# JDM2_Low_Voltage.net
KiCad netlist of a schematic drawn in EAGLE
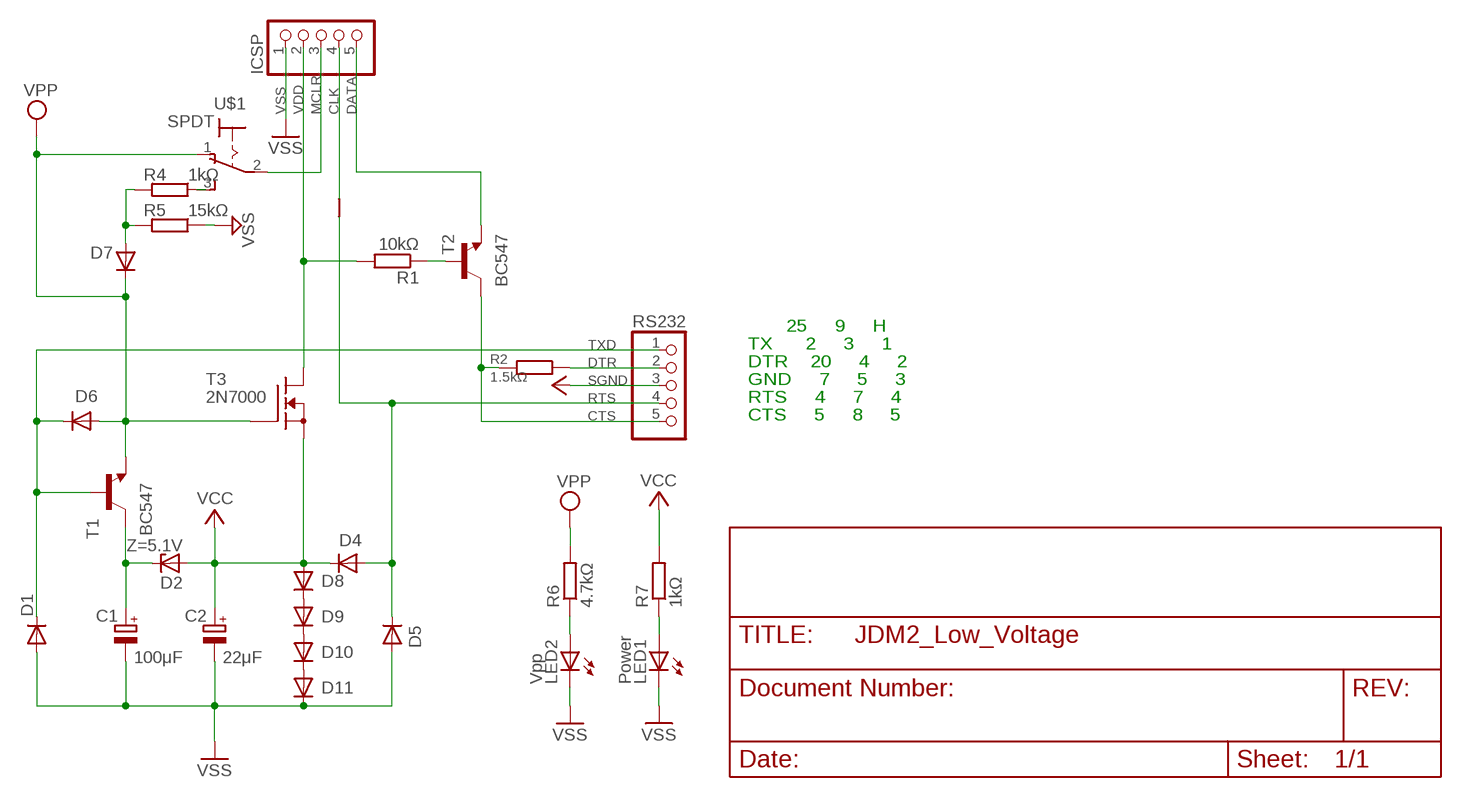
[diagram p0: schematic, sheet 1]

(export (version "E")
  (design (tool "Eeschema 10.0.6"))
  (components
    (comp (ref "C1")
      (value "100μF")
      (footprint "eagle-import:E2,5-5")
      (libsource (lib "eagle-import") (part "CPOL-EUE2.5-5"))
    )
    (comp (ref "C2")
      (value "22μF")
      (footprint "eagle-import:E2,5-5")
      (libsource (lib "eagle-import") (part "CPOL-EUE2.5-5"))
    )
    (comp (ref "D1")
      (value "1N4148")
      (footprint "eagle-import:DO35-7")
      (libsource (lib "eagle-import") (part "1N4148-7"))
    )
    (comp (ref "D2")
      (value "Z=5.1V")
      (footprint "eagle-import:DO35Z5")
      (libsource (lib "eagle-import") (part "Z-DIODEZ5"))
    )
    (comp (ref "D4")
      (value "1N4148")
      (footprint "eagle-import:DO35-2_54")
      (libsource (lib "eagle-import") (part "1N4148-2.54"))
    )
    (comp (ref "D5")
      (value "1N4148")
      (footprint "eagle-import:DO34-18")
      (libsource (lib "eagle-import") (part "1N4148-18"))
    )
    (comp (ref "D6")
      (value "1N4148")
      (footprint "eagle-import:DO35-2_54A")
      (libsource (lib "eagle-import") (part "1N4148-2.54A"))
    )
    (comp (ref "D7")
      (value "2N4148")
      (footprint "eagle-import:DO35-2_54A")
      (libsource (lib "eagle-import") (part "1N4148-2.54A"))
    )
    (comp (ref "D8")
      (value "1N4148")
      (footprint "eagle-import:DO35-2_54A")
      (libsource (lib "eagle-import") (part "1N4148-2.54A"))
    )
    (comp (ref "D9")
      (value "1N4148")
      (footprint "eagle-import:DO35-2_54A")
      (libsource (lib "eagle-import") (part "1N4148-2.54A"))
    )
    (comp (ref "D10")
      (value "1N4148")
      (footprint "eagle-import:DO35-2_54A")
      (libsource (lib "eagle-import") (part "1N4148-2.54A"))
    )
    (comp (ref "D11")
      (value "1N4148")
      (footprint "eagle-import:DO35-2_54A")
      (libsource (lib "eagle-import") (part "1N4148-2.54A"))
    )
    (comp (ref "ICSP")
      (value "PINHD-1X5")
      (footprint "eagle-import:1X05")
      (libsource (lib "eagle-import") (part "PINHD-1X5"))
    )
    (comp (ref "J1")
      (value "DUMMY")
      (footprint "eagle-import:DUMMY")
      (libsource (lib "eagle-import") (part "DUMMY"))
    )
    (comp (ref "LED1")
      (value "Power")
      (footprint "eagle-import:LED5MM")
      (libsource (lib "eagle-import") (part "LED"))
    )
    (comp (ref "LED2")
      (value "Vpp")
      (footprint "eagle-import:LED5MM")
      (libsource (lib "eagle-import") (part "LED"))
    )
    (comp (ref "R1")
      (value "10kΩ")
      (footprint "eagle-import:0207_10")
      (libsource (lib "eagle-import") (part "RES-0207-10"))
    )
    (comp (ref "R2")
      (value "1.5kΩ")
      (footprint "eagle-import:0204_7")
      (libsource (lib "eagle-import") (part "RES-0204-7"))
    )
    (comp (ref "R4")
      (value "1kΩ")
      (footprint "eagle-import:0207_10")
      (libsource (lib "eagle-import") (part "RES-0207-10"))
    )
    (comp (ref "R5")
      (value "15kΩ")
      (footprint "eagle-import:0207_10")
      (libsource (lib "eagle-import") (part "RES-0207-10"))
    )
    (comp (ref "R6")
      (value "4.7kΩ")
      (footprint "eagle-import:0204_7")
      (libsource (lib "eagle-import") (part "RES-0204-7"))
    )
    (comp (ref "R7")
      (value "1kΩ")
      (footprint "eagle-import:0204_7")
      (libsource (lib "eagle-import") (part "RES-0204-7"))
    )
    (comp (ref "RS232")
      (value "PINHD-1X5")
      (footprint "eagle-import:1X05")
      (libsource (lib "eagle-import") (part "PINHD-1X5"))
    )
    (comp (ref "T1")
      (value "BC547")
      (footprint "eagle-import:TO92-CBE")
      (libsource (lib "eagle-import") (part "BC547"))
    )
    (comp (ref "T2")
      (value "BC547")
      (footprint "eagle-import:TO92-CBE")
      (libsource (lib "eagle-import") (part "BC547"))
    )
    (comp (ref "T3")
      (value "2N7000")
      (footprint "eagle-import:TO92")
      (libsource (lib "eagle-import") (part "2N7000"))
    )
    (comp (ref "U$1")
      (value "SPDT")
      (footprint "eagle-import:SPDT")
      (libsource (lib "eagle-import") (part "SPDT"))
    )
  )
  (nets
    (net (code "1") (name "/CLK") (class "Default")
      (node (ref "ICSP") (pin "4") (pinfunction "4_4") (pintype "passive"))
      (node (ref "J1") (pin "2") (pinfunction "2_2") (pintype "passive"))
    )
    (net (code "2") (name "/CTS") (class "Default")
      (node (ref "R2") (pin "2") (pinfunction "2_2") (pintype "passive"))
      (node (ref "RS232") (pin "5") (pinfunction "5_5") (pintype "passive"))
      (node (ref "T2") (pin "C") (pinfunction "C_C") (pintype "passive"))
    )
    (net (code "3") (name "/DATA") (class "Default")
      (node (ref "ICSP") (pin "5") (pinfunction "5_5") (pintype "passive"))
      (node (ref "T2") (pin "E") (pinfunction "E_E") (pintype "passive"))
    )
    (net (code "4") (name "/DTR") (class "Default")
      (node (ref "R2") (pin "1") (pinfunction "1_1") (pintype "passive"))
      (node (ref "RS232") (pin "2") (pinfunction "2_2") (pintype "passive"))
    )
    (net (code "5") (name "/MCLR") (class "Default")
      (node (ref "ICSP") (pin "3") (pinfunction "3_3") (pintype "passive"))
      (node (ref "U$1") (pin "2") (pinfunction "P_2") (pintype "passive"))
    )
    (net (code "6") (name "/RTS") (class "Default")
      (node (ref "D4") (pin "A") (pinfunction "A_A") (pintype "passive"))
      (node (ref "D5") (pin "C") (pinfunction "C_C") (pintype "passive"))
      (node (ref "J1") (pin "1") (pinfunction "1_1") (pintype "passive"))
      (node (ref "RS232") (pin "4") (pinfunction "4_4") (pintype "passive"))
    )
    (net (code "7") (name "/TXD") (class "Default")
      (node (ref "D1") (pin "C") (pinfunction "C_C") (pintype "passive"))
      (node (ref "D6") (pin "C") (pinfunction "C_C") (pintype "passive"))
      (node (ref "RS232") (pin "1") (pinfunction "1_1") (pintype "passive"))
      (node (ref "T1") (pin "B") (pinfunction "B_B") (pintype "passive"))
    )
    (net (code "8") (name "/VDD") (class "Default")
      (node (ref "ICSP") (pin "2") (pinfunction "2_2") (pintype "passive"))
      (node (ref "R1") (pin "2") (pinfunction "2_2") (pintype "passive"))
      (node (ref "T3") (pin "3") (pinfunction "D_3") (pintype "passive"))
    )
    (net (code "9") (name "Net-(C1-Pad+)") (class "Default")
      (node (ref "C1") (pin "+") (pinfunction "+_+") (pintype "passive"))
      (node (ref "D2") (pin "C") (pinfunction "C_C") (pintype "passive"))
      (node (ref "T1") (pin "C") (pinfunction "C_C") (pintype "passive"))
    )
    (net (code "10") (name "Net-(D7-PadA)") (class "Default")
      (node (ref "D7") (pin "A") (pinfunction "A_A") (pintype "passive"))
      (node (ref "R4") (pin "2") (pinfunction "2_2") (pintype "passive"))
      (node (ref "R5") (pin "2") (pinfunction "2_2") (pintype "passive"))
    )
    (net (code "11") (name "Net-(D8-PadC)") (class "Default")
      (node (ref "D8") (pin "C") (pinfunction "C_C") (pintype "passive"))
      (node (ref "D9") (pin "A") (pinfunction "A_A") (pintype "passive"))
    )
    (net (code "12") (name "Net-(D10-PadA)") (class "Default")
      (node (ref "D10") (pin "A") (pinfunction "A_A") (pintype "passive"))
      (node (ref "D9") (pin "C") (pinfunction "C_C") (pintype "passive"))
    )
    (net (code "13") (name "Net-(D10-PadC)") (class "Default")
      (node (ref "D10") (pin "C") (pinfunction "C_C") (pintype "passive"))
      (node (ref "D11") (pin "A") (pinfunction "A_A") (pintype "passive"))
    )
    (net (code "14") (name "Net-(LED1-PadA)") (class "Default")
      (node (ref "LED1") (pin "A") (pinfunction "A_A") (pintype "passive"))
      (node (ref "R7") (pin "1") (pinfunction "1_1") (pintype "passive"))
    )
    (net (code "15") (name "Net-(LED2-PadA)") (class "Default")
      (node (ref "LED2") (pin "A") (pinfunction "A_A") (pintype "passive"))
      (node (ref "R6") (pin "1") (pinfunction "1_1") (pintype "passive"))
    )
    (net (code "16") (name "Net-(R1-Pad1)") (class "Default")
      (node (ref "R1") (pin "1") (pinfunction "1_1") (pintype "passive"))
      (node (ref "T2") (pin "B") (pinfunction "B_B") (pintype "passive"))
    )
    (net (code "17") (name "Net-(U$1-S)") (class "Default")
      (node (ref "R4") (pin "1") (pinfunction "1_1") (pintype "passive"))
      (node (ref "U$1") (pin "3") (pinfunction "S_3") (pintype "passive"))
    )
    (net (code "18") (name "VCC") (class "Default")
      (node (ref "C2") (pin "+") (pinfunction "+_+") (pintype "passive"))
      (node (ref "D2") (pin "A") (pinfunction "A_A") (pintype "passive"))
      (node (ref "D4") (pin "C") (pinfunction "C_C") (pintype "passive"))
      (node (ref "D8") (pin "A") (pinfunction "A_A") (pintype "passive"))
      (node (ref "R7") (pin "2") (pinfunction "2_2") (pintype "passive"))
      (node (ref "RS232") (pin "3") (pinfunction "3_3") (pintype "passive"))
      (node (ref "T3") (pin "1") (pinfunction "S_1") (pintype "passive"))
    )
    (net (code "19") (name "VPP") (class "Default")
      (node (ref "D6") (pin "A") (pinfunction "A_A") (pintype "passive"))
      (node (ref "D7") (pin "C") (pinfunction "C_C") (pintype "passive"))
      (node (ref "R6") (pin "2") (pinfunction "2_2") (pintype "passive"))
      (node (ref "T1") (pin "E") (pinfunction "E_E") (pintype "passive"))
      (node (ref "T3") (pin "2") (pinfunction "G_2") (pintype "passive"))
      (node (ref "U$1") (pin "1") (pinfunction "O_1") (pintype "passive"))
    )
    (net (code "20") (name "VSS") (class "Default")
      (node (ref "C1") (pin "-") (pinfunction "-_-") (pintype "passive"))
      (node (ref "C2") (pin "-") (pinfunction "-_-") (pintype "passive"))
      (node (ref "D1") (pin "A") (pinfunction "A_A") (pintype "passive"))
      (node (ref "D11") (pin "C") (pinfunction "C_C") (pintype "passive"))
      (node (ref "D5") (pin "A") (pinfunction "A_A") (pintype "passive"))
      (node (ref "ICSP") (pin "1") (pinfunction "1_1") (pintype "passive"))
      (node (ref "LED1") (pin "K") (pinfunction "C_K") (pintype "passive"))
      (node (ref "LED2") (pin "K") (pinfunction "C_K") (pintype "passive"))
      (node (ref "R5") (pin "1") (pinfunction "1_1") (pintype "passive"))
    )
  )
)
